# ADC.net
KiCad netlist of a schematic drawn in Altium Designer
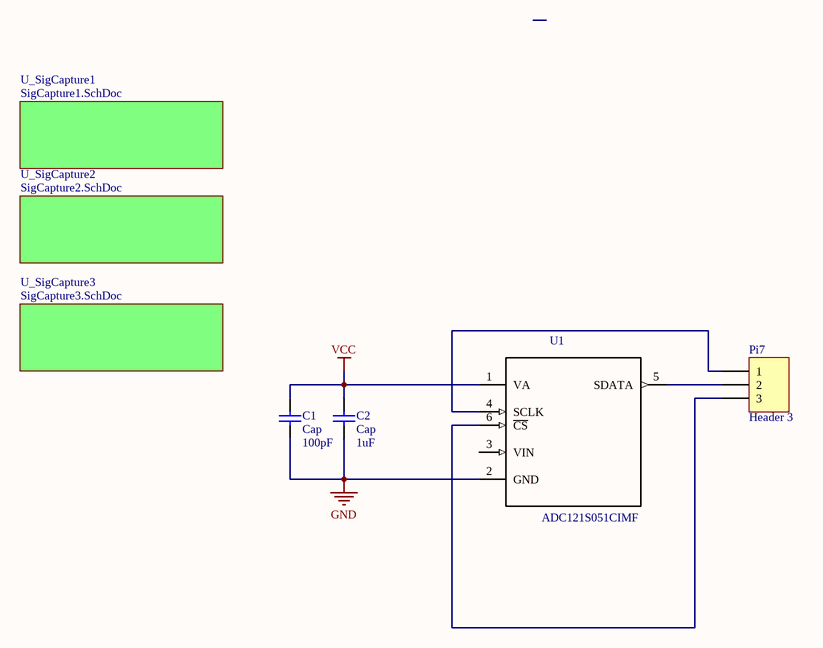
[diagram p0: ADC.SchDoc]

(export (version "E")
  (design (tool "Eeschema 10.0.6"))
  (components
    (comp (ref "C1")
      (value "Cap")
      (footprint "RAD-0.3")
      (description "Capacitor")
      (fields (field (name "ALTIUM_VALUE") "100pF") (field (name "PUBLISHER") "Altium Limited"))
      (libsource (lib "Miscellaneous Devices") (part "Cap"))
    )
    (comp (ref "C2")
      (value "Cap")
      (footprint "RAD-0.3")
      (description "Capacitor")
      (fields (field (name "ALTIUM_VALUE") "1uF") (field (name "PUBLISHER") "Altium Limited"))
      (libsource (lib "Miscellaneous Devices") (part "Cap"))
    )
    (comp (ref "Pi7")
      (value "Header 3")
      (footprint "HDR1X3")
      (description "Header, 3-Pin")
      (fields (field (name "PUBLISHER") "Altium Limited"))
      (libsource (lib "Miscellaneous Connectors") (part "Header 3"))
    )
    (comp (ref "U1")
      (value "ADC121S051CIMF")
      (footprint "SOT95P284X122-6N")
      (description "Single Channel, 200 to 500 ksps, 12-Bit A/D Converter 6-SOT-23 -40 to 85")
      (fields (field (name "MP") "ADC121S051CIMF/NOPB") (field (name "MF") "Texas Instruments"))
      (libsource (lib "ADC121S051CIMF") (part "ADC121S051CIMF"))
    )
  )
  (nets
    (net (code "1") (name "GND") (class "Default")
      (node (ref "C1") (pin "2") (pinfunction "2_2") (pintype "passive"))
      (node (ref "C2") (pin "1") (pinfunction "1_1") (pintype "passive"))
      (node (ref "U1") (pin "2") (pinfunction "GND_2") (pintype "passive"))
    )
    (net (code "2") (name "Net-(U1-SCLK)") (class "Default")
      (node (ref "Pi7") (pin "1") (pinfunction "1_1") (pintype "passive"))
      (node (ref "U1") (pin "4") (pinfunction "SCLK_4") (pintype "input"))
    )
    (net (code "3") (name "Net-(U1-SDATA)") (class "Default")
      (node (ref "Pi7") (pin "2") (pinfunction "2_2") (pintype "passive"))
      (node (ref "U1") (pin "5") (pinfunction "SDATA_5") (pintype "output"))
    )
    (net (code "4") (name "Net-(U1-~{CS})") (class "Default")
      (node (ref "Pi7") (pin "3") (pinfunction "3_3") (pintype "passive"))
      (node (ref "U1") (pin "6") (pinfunction "~{CS}_6") (pintype "input"))
    )
    (net (code "5") (name "VCC") (class "Default")
      (node (ref "C1") (pin "1") (pinfunction "1_1") (pintype "passive"))
      (node (ref "C2") (pin "2") (pinfunction "2_2") (pintype "passive"))
      (node (ref "U1") (pin "1") (pinfunction "VA_1") (pintype "power_in"))
    )
    (net (code "6") (name "unconnected-(U1-VIN-Pad3)") (class "Default")
      (node (ref "U1") (pin "3") (pinfunction "VIN_3") (pintype "input"))
    )
  )
)
